# Board.net
KiCad netlist of a schematic drawn in EAGLE
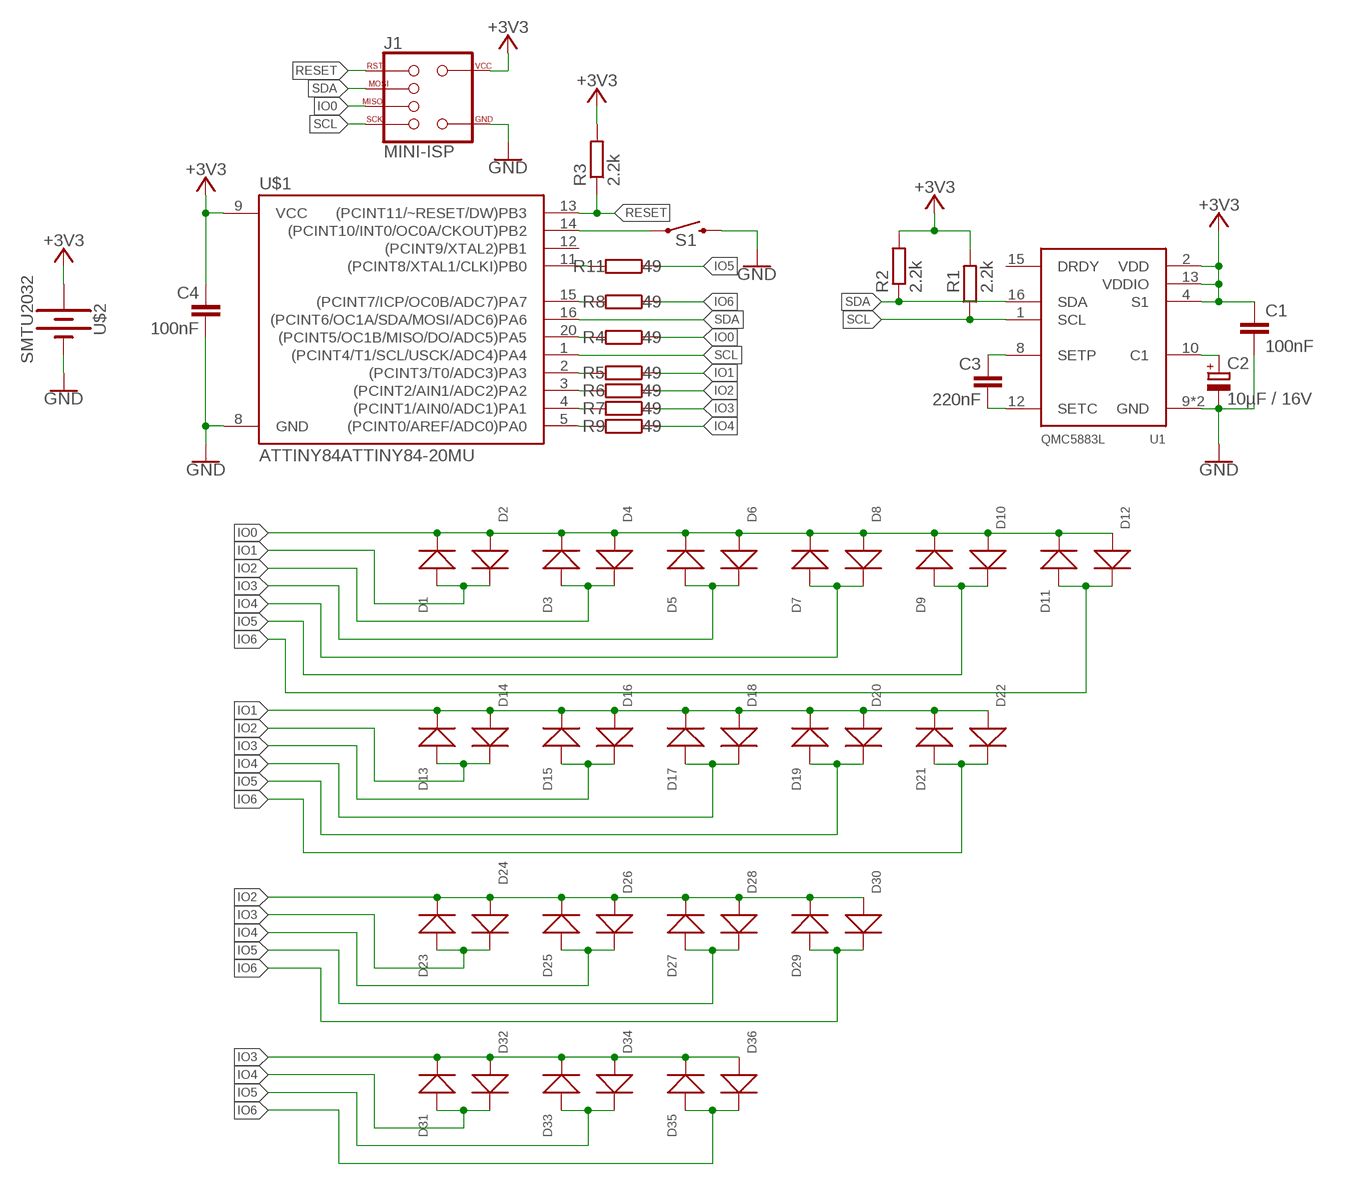
[diagram p0: schematic, sheet 1]

(export (version "E")
  (design (tool "Eeschema 10.0.6"))
  (components
    (comp (ref "C1")
      (value "100nF")
      (footprint "eagle-import:C0402K")
      (libsource (lib "eagle-import") (part "C-EUC0402K"))
    )
    (comp (ref "C2")
      (value "10µF / 16V")
      (footprint "eagle-import:CT3216")
      (libsource (lib "eagle-import") (part "CPOL-EUCT3216"))
    )
    (comp (ref "C3")
      (value "220nF")
      (footprint "eagle-import:C0402K")
      (libsource (lib "eagle-import") (part "C-EUC0402K"))
    )
    (comp (ref "C4")
      (value "100nF")
      (footprint "eagle-import:C0402K")
      (libsource (lib "eagle-import") (part "C-EUC0402K"))
    )
    (comp (ref "D1")
      (value "RED")
      (footprint "eagle-import:SOD-523")
      (libsource (lib "eagle-import") (part "DIODE'0603'"))
    )
    (comp (ref "D2")
      (value "RED")
      (footprint "eagle-import:SOD-523")
      (libsource (lib "eagle-import") (part "DIODE'0603'"))
    )
    (comp (ref "D3")
      (value "RED")
      (footprint "eagle-import:SOD-523")
      (libsource (lib "eagle-import") (part "DIODE'0603'"))
    )
    (comp (ref "D4")
      (value "RED")
      (footprint "eagle-import:SOD-523")
      (libsource (lib "eagle-import") (part "DIODE'0603'"))
    )
    (comp (ref "D5")
      (value "RED")
      (footprint "eagle-import:SOD-523")
      (libsource (lib "eagle-import") (part "DIODE'0603'"))
    )
    (comp (ref "D6")
      (value "RED")
      (footprint "eagle-import:SOD-523")
      (libsource (lib "eagle-import") (part "DIODE'0603'"))
    )
    (comp (ref "D7")
      (value "RED")
      (footprint "eagle-import:SOD-523")
      (libsource (lib "eagle-import") (part "DIODE'0603'"))
    )
    (comp (ref "D8")
      (value "RED")
      (footprint "eagle-import:SOD-523")
      (libsource (lib "eagle-import") (part "DIODE'0603'"))
    )
    (comp (ref "D9")
      (value "YELLOW")
      (footprint "eagle-import:SOD-523")
      (libsource (lib "eagle-import") (part "DIODE'0603'"))
    )
    (comp (ref "D10")
      (value "RED")
      (footprint "eagle-import:SOD-523")
      (libsource (lib "eagle-import") (part "DIODE'0603'"))
    )
    (comp (ref "D11")
      (value "RED")
      (footprint "eagle-import:SOD-523")
      (libsource (lib "eagle-import") (part "DIODE'0603'"))
    )
    (comp (ref "D12")
      (value "RED")
      (footprint "eagle-import:SOD-523")
      (libsource (lib "eagle-import") (part "DIODE'0603'"))
    )
    (comp (ref "D13")
      (value "RED")
      (footprint "eagle-import:SOD-523")
      (libsource (lib "eagle-import") (part "DIODE'0603'"))
    )
    (comp (ref "D14")
      (value "RED")
      (footprint "eagle-import:SOD-523")
      (libsource (lib "eagle-import") (part "DIODE'0603'"))
    )
    (comp (ref "D15")
      (value "RED")
      (footprint "eagle-import:SOD-523")
      (libsource (lib "eagle-import") (part "DIODE'0603'"))
    )
    (comp (ref "D16")
      (value "RED")
      (footprint "eagle-import:SOD-523")
      (libsource (lib "eagle-import") (part "DIODE'0603'"))
    )
    (comp (ref "D17")
      (value "RED")
      (footprint "eagle-import:SOD-523")
      (libsource (lib "eagle-import") (part "DIODE'0603'"))
    )
    (comp (ref "D18")
      (value "YELLOW")
      (footprint "eagle-import:SOD-523")
      (libsource (lib "eagle-import") (part "DIODE'0603'"))
    )
    (comp (ref "D19")
      (value "RED")
      (footprint "eagle-import:SOD-523")
      (libsource (lib "eagle-import") (part "DIODE'0603'"))
    )
    (comp (ref "D20")
      (value "RED")
      (footprint "eagle-import:SOD-523")
      (libsource (lib "eagle-import") (part "DIODE'0603'"))
    )
    (comp (ref "D21")
      (value "RED")
      (footprint "eagle-import:SOD-523")
      (libsource (lib "eagle-import") (part "DIODE'0603'"))
    )
    (comp (ref "D22")
      (value "RED")
      (footprint "eagle-import:SOD-523")
      (libsource (lib "eagle-import") (part "DIODE'0603'"))
    )
    (comp (ref "D23")
      (value "RED")
      (footprint "eagle-import:SOD-523")
      (libsource (lib "eagle-import") (part "DIODE'0603'"))
    )
    (comp (ref "D24")
      (value "RED")
      (footprint "eagle-import:SOD-523")
      (libsource (lib "eagle-import") (part "DIODE'0603'"))
    )
    (comp (ref "D25")
      (value "RED")
      (footprint "eagle-import:SOD-523")
      (libsource (lib "eagle-import") (part "DIODE'0603'"))
    )
    (comp (ref "D26")
      (value "RED")
      (footprint "eagle-import:SOD-523")
      (libsource (lib "eagle-import") (part "DIODE'0603'"))
    )
    (comp (ref "D27")
      (value "YELLOW")
      (footprint "eagle-import:SOD-523")
      (libsource (lib "eagle-import") (part "DIODE'0603'"))
    )
    (comp (ref "D28")
      (value "RED")
      (footprint "eagle-import:SOD-523")
      (libsource (lib "eagle-import") (part "DIODE'0603'"))
    )
    (comp (ref "D29")
      (value "RED")
      (footprint "eagle-import:SOD-523")
      (libsource (lib "eagle-import") (part "DIODE'0603'"))
    )
    (comp (ref "D30")
      (value "RED")
      (footprint "eagle-import:SOD-523")
      (libsource (lib "eagle-import") (part "DIODE'0603'"))
    )
    (comp (ref "D31")
      (value "RED")
      (footprint "eagle-import:SOD-523")
      (libsource (lib "eagle-import") (part "DIODE'0603'"))
    )
    (comp (ref "D32")
      (value "RED")
      (footprint "eagle-import:SOD-523")
      (libsource (lib "eagle-import") (part "DIODE'0603'"))
    )
    (comp (ref "D33")
      (value "RED")
      (footprint "eagle-import:SOD-523")
      (libsource (lib "eagle-import") (part "DIODE'0603'"))
    )
    (comp (ref "D34")
      (value "RED")
      (footprint "eagle-import:SOD-523")
      (libsource (lib "eagle-import") (part "DIODE'0603'"))
    )
    (comp (ref "D35")
      (value "RED")
      (footprint "eagle-import:SOD-523")
      (libsource (lib "eagle-import") (part "DIODE'0603'"))
    )
    (comp (ref "D36")
      (value "YELLOW")
      (footprint "eagle-import:SOD-523")
      (libsource (lib "eagle-import") (part "DIODE'0603'"))
    )
    (comp (ref "J1")
      (value "MINI-ISP")
      (footprint "eagle-import:MINI-ISP")
      (libsource (lib "eagle-import") (part "MINI-ISP"))
    )
    (comp (ref "R1")
      (value "2.2k")
      (footprint "eagle-import:R0402")
      (libsource (lib "eagle-import") (part "R-EU_R0402"))
    )
    (comp (ref "R2")
      (value "2.2k")
      (footprint "eagle-import:R0402")
      (libsource (lib "eagle-import") (part "R-EU_R0402"))
    )
    (comp (ref "R3")
      (value "2.2k")
      (footprint "eagle-import:R0402")
      (libsource (lib "eagle-import") (part "R-EU_R0402"))
    )
    (comp (ref "R4")
      (value "49")
      (footprint "eagle-import:R0402")
      (libsource (lib "eagle-import") (part "R-EU_R0402"))
    )
    (comp (ref "R5")
      (value "49")
      (footprint "eagle-import:R0402")
      (libsource (lib "eagle-import") (part "R-EU_R0402"))
    )
    (comp (ref "R6")
      (value "49")
      (footprint "eagle-import:R0402")
      (libsource (lib "eagle-import") (part "R-EU_R0402"))
    )
    (comp (ref "R7")
      (value "49")
      (footprint "eagle-import:R0402")
      (libsource (lib "eagle-import") (part "R-EU_R0402"))
    )
    (comp (ref "R8")
      (value "49")
      (footprint "eagle-import:R0402")
      (libsource (lib "eagle-import") (part "R-EU_R0402"))
    )
    (comp (ref "R9")
      (value "49")
      (footprint "eagle-import:R0402")
      (libsource (lib "eagle-import") (part "R-EU_R0402"))
    )
    (comp (ref "R11")
      (value "49")
      (footprint "eagle-import:R0402")
      (libsource (lib "eagle-import") (part "R-EU_R0402"))
    )
    (comp (ref "S1")
      (value "MOMENTARY-SWITCH-SPST-SMD-5.2MM")
      (footprint "eagle-import:TACTILE_SWITCH_SMD_5.2MM")
      (libsource (lib "eagle-import") (part "MOMENTARY-SWITCH-SPST-SMD-5.2MM"))
    )
    (comp (ref "U$1")
      (value "ATTINY84ATTINY84-20MU")
      (footprint "eagle-import:QFN20")
      (libsource (lib "eagle-import") (part "ATTINY84ATTINY84-20MU"))
    )
    (comp (ref "U$2")
      (value "SMTU2032")
      (footprint "eagle-import:SMTU2032")
      (libsource (lib "eagle-import") (part "SMTU2032"))
    )
    (comp (ref "U1")
      (value "QMC5883L")
      (footprint "eagle-import:QFN50P300X300X102-16N")
      (libsource (lib "eagle-import") (part "QMC5883L"))
    )
  )
  (nets
    (net (code "1") (name "+3V3") (class "Default")
      (node (ref "C1") (pin "1") (pinfunction "1_1") (pintype "passive"))
      (node (ref "C4") (pin "1") (pinfunction "1_1") (pintype "passive"))
      (node (ref "J1") (pin "VDD") (pinfunction "2_VDD") (pintype "passive"))
      (node (ref "R1") (pin "2") (pinfunction "2_2") (pintype "passive"))
      (node (ref "R2") (pin "2") (pinfunction "2_2") (pintype "passive"))
      (node (ref "R3") (pin "2") (pinfunction "2_2") (pintype "passive"))
      (node (ref "U$1") (pin "9") (pinfunction "VCC_9") (pintype "bidirectional"))
      (node (ref "U$2") (pin "POS") (pinfunction "+_POS") (pintype "power_in"))
      (node (ref "U1") (pin "13") (pinfunction "VDDIO_13") (pintype "power_in"))
      (node (ref "U1") (pin "2") (pinfunction "VDD_2") (pintype "power_in"))
      (node (ref "U1") (pin "4") (pinfunction "S1_4") (pintype "power_in"))
    )
    (net (code "2") (name "GND") (class "Default")
      (node (ref "C1") (pin "2") (pinfunction "2_2") (pintype "passive"))
      (node (ref "C2") (pin "-") (pinfunction "-_-") (pintype "passive"))
      (node (ref "C4") (pin "2") (pinfunction "2_2") (pintype "passive"))
      (node (ref "J1") (pin "GND") (pinfunction "6_GND") (pintype "passive"))
      (node (ref "S1") (pin "3") (pinfunction "2_3") (pintype "passive"))
      (node (ref "U$1") (pin "8") (pinfunction "GND_8") (pintype "bidirectional"))
      (node (ref "U$2") (pin "NEG") (pinfunction "-_NEG") (pintype "power_in"))
      (node (ref "U1") (pin "11") (pinfunction "GND_11") (pintype "power_in"))
      (node (ref "U1") (pin "9") (pinfunction "GND_9") (pintype "power_in"))
    )
    (net (code "3") (name "IO0") (class "Default")
      (node (ref "D1") (pin "-") (pinfunction "-_-") (pintype "passive"))
      (node (ref "D10") (pin "+") (pinfunction "+_+") (pintype "passive"))
      (node (ref "D11") (pin "-") (pinfunction "-_-") (pintype "passive"))
      (node (ref "D12") (pin "+") (pinfunction "+_+") (pintype "passive"))
      (node (ref "D2") (pin "+") (pinfunction "+_+") (pintype "passive"))
      (node (ref "D3") (pin "-") (pinfunction "-_-") (pintype "passive"))
      (node (ref "D4") (pin "+") (pinfunction "+_+") (pintype "passive"))
      (node (ref "D5") (pin "-") (pinfunction "-_-") (pintype "passive"))
      (node (ref "D6") (pin "+") (pinfunction "+_+") (pintype "passive"))
      (node (ref "D7") (pin "-") (pinfunction "-_-") (pintype "passive"))
      (node (ref "D8") (pin "+") (pinfunction "+_+") (pintype "passive"))
      (node (ref "D9") (pin "-") (pinfunction "-_-") (pintype "passive"))
      (node (ref "J1") (pin "MISO") (pinfunction "1_MISO") (pintype "passive"))
      (node (ref "R4") (pin "1") (pinfunction "1_1") (pintype "passive"))
    )
    (net (code "4") (name "IO1") (class "Default")
      (node (ref "D1") (pin "+") (pinfunction "+_+") (pintype "passive"))
      (node (ref "D13") (pin "-") (pinfunction "-_-") (pintype "passive"))
      (node (ref "D14") (pin "+") (pinfunction "+_+") (pintype "passive"))
      (node (ref "D15") (pin "-") (pinfunction "-_-") (pintype "passive"))
      (node (ref "D16") (pin "+") (pinfunction "+_+") (pintype "passive"))
      (node (ref "D17") (pin "-") (pinfunction "-_-") (pintype "passive"))
      (node (ref "D18") (pin "+") (pinfunction "+_+") (pintype "passive"))
      (node (ref "D19") (pin "-") (pinfunction "-_-") (pintype "passive"))
      (node (ref "D2") (pin "-") (pinfunction "-_-") (pintype "passive"))
      (node (ref "D20") (pin "+") (pinfunction "+_+") (pintype "passive"))
      (node (ref "D21") (pin "-") (pinfunction "-_-") (pintype "passive"))
      (node (ref "D22") (pin "+") (pinfunction "+_+") (pintype "passive"))
      (node (ref "R5") (pin "1") (pinfunction "1_1") (pintype "passive"))
    )
    (net (code "5") (name "IO2") (class "Default")
      (node (ref "D13") (pin "+") (pinfunction "+_+") (pintype "passive"))
      (node (ref "D14") (pin "-") (pinfunction "-_-") (pintype "passive"))
      (node (ref "D23") (pin "-") (pinfunction "-_-") (pintype "passive"))
      (node (ref "D24") (pin "+") (pinfunction "+_+") (pintype "passive"))
      (node (ref "D25") (pin "-") (pinfunction "-_-") (pintype "passive"))
      (node (ref "D26") (pin "+") (pinfunction "+_+") (pintype "passive"))
      (node (ref "D27") (pin "-") (pinfunction "-_-") (pintype "passive"))
      (node (ref "D28") (pin "+") (pinfunction "+_+") (pintype "passive"))
      (node (ref "D29") (pin "-") (pinfunction "-_-") (pintype "passive"))
      (node (ref "D3") (pin "+") (pinfunction "+_+") (pintype "passive"))
      (node (ref "D30") (pin "+") (pinfunction "+_+") (pintype "passive"))
      (node (ref "D4") (pin "-") (pinfunction "-_-") (pintype "passive"))
      (node (ref "R6") (pin "1") (pinfunction "1_1") (pintype "passive"))
    )
    (net (code "6") (name "IO3") (class "Default")
      (node (ref "D15") (pin "+") (pinfunction "+_+") (pintype "passive"))
      (node (ref "D16") (pin "-") (pinfunction "-_-") (pintype "passive"))
      (node (ref "D23") (pin "+") (pinfunction "+_+") (pintype "passive"))
      (node (ref "D24") (pin "-") (pinfunction "-_-") (pintype "passive"))
      (node (ref "D31") (pin "-") (pinfunction "-_-") (pintype "passive"))
      (node (ref "D32") (pin "+") (pinfunction "+_+") (pintype "passive"))
      (node (ref "D33") (pin "-") (pinfunction "-_-") (pintype "passive"))
      (node (ref "D34") (pin "+") (pinfunction "+_+") (pintype "passive"))
      (node (ref "D35") (pin "-") (pinfunction "-_-") (pintype "passive"))
      (node (ref "D36") (pin "+") (pinfunction "+_+") (pintype "passive"))
      (node (ref "D5") (pin "+") (pinfunction "+_+") (pintype "passive"))
      (node (ref "D6") (pin "-") (pinfunction "-_-") (pintype "passive"))
      (node (ref "R7") (pin "1") (pinfunction "1_1") (pintype "passive"))
    )
    (net (code "7") (name "IO4") (class "Default")
      (node (ref "D17") (pin "+") (pinfunction "+_+") (pintype "passive"))
      (node (ref "D18") (pin "-") (pinfunction "-_-") (pintype "passive"))
      (node (ref "D25") (pin "+") (pinfunction "+_+") (pintype "passive"))
      (node (ref "D26") (pin "-") (pinfunction "-_-") (pintype "passive"))
      (node (ref "D31") (pin "+") (pinfunction "+_+") (pintype "passive"))
      (node (ref "D32") (pin "-") (pinfunction "-_-") (pintype "passive"))
      (node (ref "D7") (pin "+") (pinfunction "+_+") (pintype "passive"))
      (node (ref "D8") (pin "-") (pinfunction "-_-") (pintype "passive"))
      (node (ref "R9") (pin "1") (pinfunction "1_1") (pintype "passive"))
    )
    (net (code "8") (name "IO5") (class "Default")
      (node (ref "D10") (pin "-") (pinfunction "-_-") (pintype "passive"))
      (node (ref "D19") (pin "+") (pinfunction "+_+") (pintype "passive"))
      (node (ref "D20") (pin "-") (pinfunction "-_-") (pintype "passive"))
      (node (ref "D27") (pin "+") (pinfunction "+_+") (pintype "passive"))
      (node (ref "D28") (pin "-") (pinfunction "-_-") (pintype "passive"))
      (node (ref "D33") (pin "+") (pinfunction "+_+") (pintype "passive"))
      (node (ref "D34") (pin "-") (pinfunction "-_-") (pintype "passive"))
      (node (ref "D9") (pin "+") (pinfunction "+_+") (pintype "passive"))
      (node (ref "R11") (pin "1") (pinfunction "1_1") (pintype "passive"))
    )
    (net (code "9") (name "IO6") (class "Default")
      (node (ref "D11") (pin "+") (pinfunction "+_+") (pintype "passive"))
      (node (ref "D12") (pin "-") (pinfunction "-_-") (pintype "passive"))
      (node (ref "D21") (pin "+") (pinfunction "+_+") (pintype "passive"))
      (node (ref "D22") (pin "-") (pinfunction "-_-") (pintype "passive"))
      (node (ref "D29") (pin "+") (pinfunction "+_+") (pintype "passive"))
      (node (ref "D30") (pin "-") (pinfunction "-_-") (pintype "passive"))
      (node (ref "D35") (pin "+") (pinfunction "+_+") (pintype "passive"))
      (node (ref "D36") (pin "-") (pinfunction "-_-") (pintype "passive"))
      (node (ref "R8") (pin "1") (pinfunction "1_1") (pintype "passive"))
    )
    (net (code "10") (name "Net-(U$1-(PCINT0{slash}AREF{slash}ADC0)PA0)") (class "Default")
      (node (ref "R9") (pin "2") (pinfunction "2_2") (pintype "passive"))
      (node (ref "U$1") (pin "5") (pinfunction "(PCINT0/AREF/ADC0)PA0_5") (pintype "bidirectional"))
    )
    (net (code "11") (name "Net-(U$1-(PCINT1{slash}AIN0{slash}ADC1)PA1)") (class "Default")
      (node (ref "R7") (pin "2") (pinfunction "2_2") (pintype "passive"))
      (node (ref "U$1") (pin "4") (pinfunction "(PCINT1/AIN0/ADC1)PA1_4") (pintype "bidirectional"))
    )
    (net (code "12") (name "Net-(U$1-(PCINT2{slash}AIN1{slash}ADC2)PA2)") (class "Default")
      (node (ref "R6") (pin "2") (pinfunction "2_2") (pintype "passive"))
      (node (ref "U$1") (pin "3") (pinfunction "(PCINT2/AIN1/ADC2)PA2_3") (pintype "bidirectional"))
    )
    (net (code "13") (name "Net-(U$1-(PCINT3{slash}T0{slash}ADC3)PA3)") (class "Default")
      (node (ref "R5") (pin "2") (pinfunction "2_2") (pintype "passive"))
      (node (ref "U$1") (pin "2") (pinfunction "(PCINT3/T0/ADC3)PA3_2") (pintype "bidirectional"))
    )
    (net (code "14") (name "Net-(U$1-(PCINT5{slash}OC1B{slash}MISO{slash}DO{slash}ADC5)PA5)") (class "Default")
      (node (ref "R4") (pin "2") (pinfunction "2_2") (pintype "passive"))
      (node (ref "U$1") (pin "20") (pinfunction "(PCINT5/OC1B/MISO/DO/ADC5)PA5_20") (pintype "bidirectional"))
    )
    (net (code "15") (name "Net-(U$1-(PCINT7{slash}ICP{slash}OC0B{slash}ADC7)PA7)") (class "Default")
      (node (ref "R8") (pin "2") (pinfunction "2_2") (pintype "passive"))
      (node (ref "U$1") (pin "15") (pinfunction "(PCINT7/ICP/OC0B/ADC7)PA7_15") (pintype "bidirectional"))
    )
    (net (code "16") (name "Net-(U$1-(PCINT8{slash}XTAL1{slash}CLKI)PB0)") (class "Default")
      (node (ref "R11") (pin "2") (pinfunction "2_2") (pintype "passive"))
      (node (ref "U$1") (pin "11") (pinfunction "(PCINT8/XTAL1/CLKI)PB0_11") (pintype "bidirectional"))
    )
    (net (code "17") (name "Net-(U$1-(PCINT10{slash}INT0{slash}OC0A{slash}CKOUT)PB2)") (class "Default")
      (node (ref "S1") (pin "1") (pinfunction "1_1") (pintype "passive"))
      (node (ref "U$1") (pin "14") (pinfunction "(PCINT10/INT0/OC0A/CKOUT)PB2_14") (pintype "bidirectional"))
    )
    (net (code "18") (name "Net-(U1-C1)") (class "Default")
      (node (ref "C2") (pin "+") (pinfunction "+_+") (pintype "passive"))
      (node (ref "U1") (pin "10") (pinfunction "C1_10") (pintype "passive"))
    )
    (net (code "19") (name "Net-(U1-SETC)") (class "Default")
      (node (ref "C3") (pin "2") (pinfunction "2_2") (pintype "passive"))
      (node (ref "U1") (pin "12") (pinfunction "SETC_12") (pintype "passive"))
    )
    (net (code "20") (name "Net-(U1-SETP)") (class "Default")
      (node (ref "C3") (pin "1") (pinfunction "1_1") (pintype "passive"))
      (node (ref "U1") (pin "8") (pinfunction "SETP_8") (pintype "passive"))
    )
    (net (code "21") (name "RESET") (class "Default")
      (node (ref "J1") (pin "RESET") (pinfunction "5_RESET") (pintype "passive"))
      (node (ref "R3") (pin "1") (pinfunction "1_1") (pintype "passive"))
      (node (ref "U$1") (pin "13") (pinfunction "(PCINT11/~{RESET/DW})PB3_13") (pintype "bidirectional"))
    )
    (net (code "22") (name "SCL") (class "Default")
      (node (ref "J1") (pin "SCK") (pinfunction "3_SCK") (pintype "passive"))
      (node (ref "R1") (pin "1") (pinfunction "1_1") (pintype "passive"))
      (node (ref "U$1") (pin "1") (pinfunction "(PCINT4/T1/SCL/USCK/ADC4)PA4_1") (pintype "bidirectional"))
      (node (ref "U1") (pin "1") (pinfunction "SCL_1") (pintype "input"))
    )
    (net (code "23") (name "SDA") (class "Default")
      (node (ref "J1") (pin "MOSI") (pinfunction "4_MOSI") (pintype "passive"))
      (node (ref "R2") (pin "1") (pinfunction "1_1") (pintype "passive"))
      (node (ref "U$1") (pin "16") (pinfunction "(PCINT6/OC1A/SDA/MOSI/ADC6)PA6_16") (pintype "bidirectional"))
      (node (ref "U1") (pin "16") (pinfunction "SDA_16") (pintype "bidirectional"))
    )
    (net (code "24") (name "unconnected-(U$1-(PCINT9{slash}XTAL2)PB1-Pad12)") (class "Default")
      (node (ref "U$1") (pin "12") (pinfunction "(PCINT9/XTAL2)PB1_12") (pintype "bidirectional"))
    )
    (net (code "25") (name "unconnected-(U1-DRDY-Pad15)") (class "Default")
      (node (ref "U1") (pin "15") (pinfunction "DRDY_15") (pintype "output"))
    )
  )
)
